# DCDeluxe.net
KiCad netlist of a schematic drawn in EAGLE
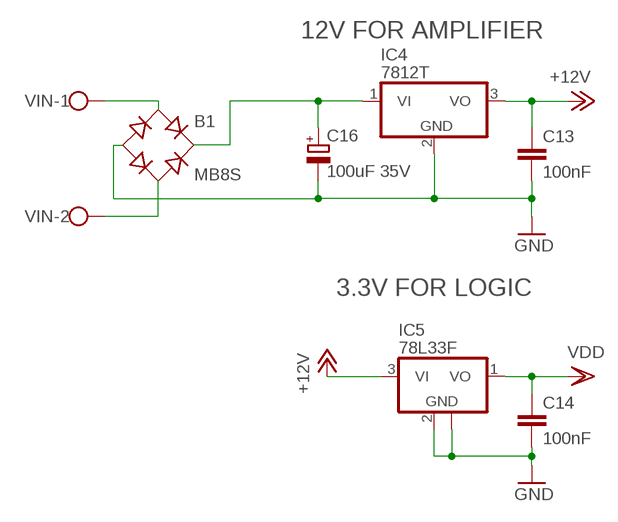
[diagram p0: schematic, sheet 1]
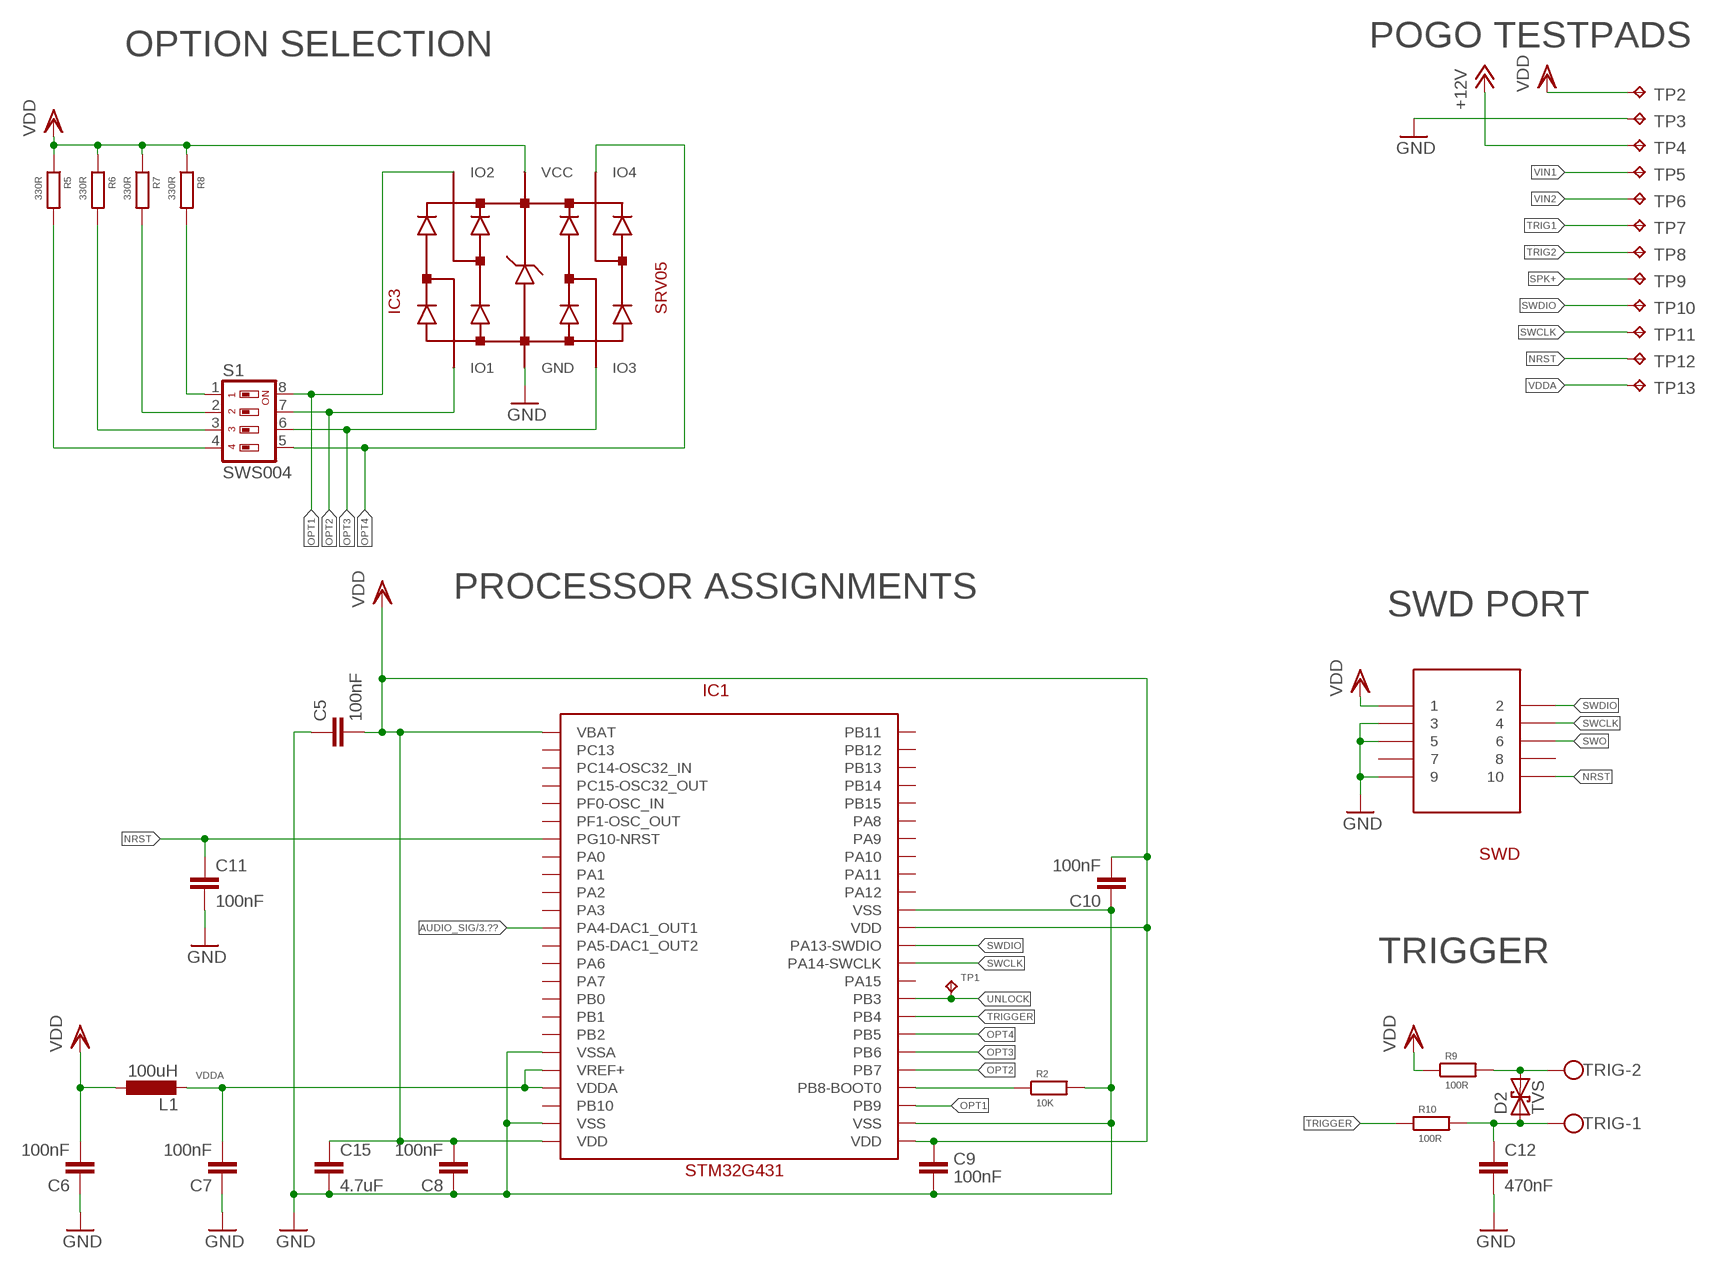
[diagram p1: schematic, sheet 2]
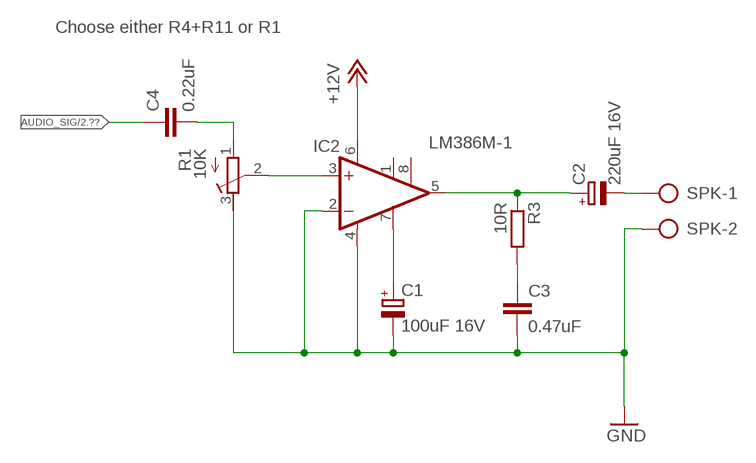
[diagram p2: schematic, sheet 3]

(export (version "E")
  (design (tool "Eeschema 10.0.6"))
  (components
    (comp (ref "B1")
      (value "MB8S")
      (footprint "eagle-import:SOIC-4")
      (libsource (lib "eagle-import") (part "MBS8"))
    )
    (comp (ref "C13")
      (value "100nF")
      (footprint "eagle-import:C0603")
      (libsource (lib "eagle-import") (part "C-EUC0603"))
    )
    (comp (ref "C14")
      (value "100nF")
      (footprint "eagle-import:C0603")
      (libsource (lib "eagle-import") (part "C-EUC0603"))
    )
    (comp (ref "C16")
      (value "100uF 35V")
      (footprint "eagle-import:153CLV-0807")
      (libsource (lib "eagle-import") (part "CPOL-EU153CLV-0807"))
    )
    (comp (ref "IC4")
      (value "7812T")
      (footprint "eagle-import:TO220H")
      (libsource (lib "eagle-import") (part "78T12"))
    )
    (comp (ref "IC5")
      (value "78L33F")
      (footprint "eagle-import:SOT89")
      (libsource (lib "eagle-import") (part "78LF05"))
    )
    (comp (ref "VIN")
      (value "W237-102")
      (footprint "eagle-import:W237-102")
      (fields (field (name "MPN") "237-102"))
      (libsource (lib "eagle-import") (part "W237-102"))
    )
    (comp (ref "C1")
      (value "100uF 16V")
      (footprint "eagle-import:153CLV-0605")
      (libsource (lib "eagle-import") (part "CPOL-EU153CLV-0605"))
    )
    (comp (ref "C2")
      (value "220uF 16V")
      (footprint "eagle-import:153CLV-0605")
      (libsource (lib "eagle-import") (part "CPOL-EU153CLV-0605"))
    )
    (comp (ref "C3")
      (value "0.47uF")
      (footprint "eagle-import:C0603")
      (libsource (lib "eagle-import") (part "C-EUC0603"))
    )
    (comp (ref "C4")
      (value "0.22uF")
      (footprint "eagle-import:C0603")
      (libsource (lib "eagle-import") (part "C-EUC0603"))
    )
    (comp (ref "IC2")
      (value "LM386M-1")
      (footprint "eagle-import:SO08")
      (libsource (lib "eagle-import") (part "LM386?-M1"))
    )
    (comp (ref "R1")
      (value "10K")
      (footprint "eagle-import:RTRIM3339P")
      (libsource (lib "eagle-import") (part "R-TRIMM3339P"))
    )
    (comp (ref "R3")
      (value "10R")
      (footprint "eagle-import:R0805")
      (libsource (lib "eagle-import") (part "R-EU_R0805"))
    )
    (comp (ref "SPK")
      (value "W237-102")
      (footprint "eagle-import:W237-102")
      (fields (field (name "MPN") "237-102"))
      (libsource (lib "eagle-import") (part "W237-102"))
    )
    (comp (ref "C5")
      (value "100nF")
      (footprint "eagle-import:C0603")
      (libsource (lib "eagle-import") (part "C-EUC0603"))
    )
    (comp (ref "C6")
      (value "100nF")
      (footprint "eagle-import:C0603")
      (libsource (lib "eagle-import") (part "C-EUC0603"))
    )
    (comp (ref "C7")
      (value "100nF")
      (footprint "eagle-import:C0603")
      (libsource (lib "eagle-import") (part "C-EUC0603"))
    )
    (comp (ref "C8")
      (value "100nF")
      (footprint "eagle-import:C0603")
      (libsource (lib "eagle-import") (part "C-EUC0603"))
    )
    (comp (ref "C9")
      (value "100nF")
      (footprint "eagle-import:C0603")
      (libsource (lib "eagle-import") (part "C-EUC0603"))
    )
    (comp (ref "C10")
      (value "100nF")
      (footprint "eagle-import:C0603")
      (libsource (lib "eagle-import") (part "C-EUC0603"))
    )
    (comp (ref "C11")
      (value "100nF")
      (footprint "eagle-import:C0603")
      (libsource (lib "eagle-import") (part "C-EUC0603"))
    )
    (comp (ref "C12")
      (value "470nF")
      (footprint "eagle-import:C0603")
      (libsource (lib "eagle-import") (part "C-EUC0603"))
    )
    (comp (ref "C15")
      (value "4.7uF")
      (footprint "eagle-import:C0603")
      (libsource (lib "eagle-import") (part "C-EUC0603"))
    )
    (comp (ref "D2")
      (value "TVS")
      (footprint "eagle-import:SMA-DIODE")
      (libsource (lib "eagle-import") (part "TVS"))
    )
    (comp (ref "IC1")
      (value "STM32G431")
      (footprint "eagle-import:TQFP48")
      (libsource (lib "eagle-import") (part "STM32G431-C8T6"))
    )
    (comp (ref "IC3")
      (value "SRV05")
      (footprint "eagle-import:TSOP-6")
      (libsource (lib "eagle-import") (part "SRV05-TSOP6"))
    )
    (comp (ref "L1")
      (value "100uH")
      (footprint "eagle-import:L3225M")
      (libsource (lib "eagle-import") (part "L-EUL3225M"))
    )
    (comp (ref "R2")
      (value "10K")
      (footprint "eagle-import:R0603")
      (libsource (lib "eagle-import") (part "R-EU_R0603"))
    )
    (comp (ref "R5")
      (value "330R")
      (footprint "eagle-import:R0603")
      (libsource (lib "eagle-import") (part "R-EU_R0603"))
    )
    (comp (ref "R6")
      (value "330R")
      (footprint "eagle-import:R0603")
      (libsource (lib "eagle-import") (part "R-EU_R0603"))
    )
    (comp (ref "R7")
      (value "330R")
      (footprint "eagle-import:R0603")
      (libsource (lib "eagle-import") (part "R-EU_R0603"))
    )
    (comp (ref "R8")
      (value "330R")
      (footprint "eagle-import:R0603")
      (libsource (lib "eagle-import") (part "R-EU_R0603"))
    )
    (comp (ref "R9")
      (value "100R")
      (footprint "eagle-import:R0603")
      (libsource (lib "eagle-import") (part "R-EU_R0603"))
    )
    (comp (ref "R10")
      (value "100R")
      (footprint "eagle-import:R0603")
      (libsource (lib "eagle-import") (part "R-EU_R0603"))
    )
    (comp (ref "S1")
      (value "SWS004")
      (footprint "eagle-import:SMS-004")
      (libsource (lib "eagle-import") (part "SWS004"))
    )
    (comp (ref "SWD")
      (value "FTSH-105-01")
      (footprint "eagle-import:FTSH-105-01-XXX-DV-K")
      (libsource (lib "eagle-import") (part "FTSH-105-01"))
    )
    (comp (ref "TP1")
      (value "TPTP12R")
      (footprint "eagle-import:TP12R")
      (libsource (lib "eagle-import") (part "TPTP12R"))
    )
    (comp (ref "TP2")
      (value "TPTP20R")
      (footprint "eagle-import:TP20R")
      (libsource (lib "eagle-import") (part "TPTP20R"))
    )
    (comp (ref "TP3")
      (value "TPTP20R")
      (footprint "eagle-import:TP20R")
      (libsource (lib "eagle-import") (part "TPTP20R"))
    )
    (comp (ref "TP4")
      (value "TPTP20R")
      (footprint "eagle-import:TP20R")
      (libsource (lib "eagle-import") (part "TPTP20R"))
    )
    (comp (ref "TP5")
      (value "TPTP20R")
      (footprint "eagle-import:TP20R")
      (libsource (lib "eagle-import") (part "TPTP20R"))
    )
    (comp (ref "TP6")
      (value "TPTP20R")
      (footprint "eagle-import:TP20R")
      (libsource (lib "eagle-import") (part "TPTP20R"))
    )
    (comp (ref "TP7")
      (value "TPTP20R")
      (footprint "eagle-import:TP20R")
      (libsource (lib "eagle-import") (part "TPTP20R"))
    )
    (comp (ref "TP8")
      (value "TPTP20R")
      (footprint "eagle-import:TP20R")
      (libsource (lib "eagle-import") (part "TPTP20R"))
    )
    (comp (ref "TP9")
      (value "TPTP20R")
      (footprint "eagle-import:TP20R")
      (libsource (lib "eagle-import") (part "TPTP20R"))
    )
    (comp (ref "TP10")
      (value "TPTP20R")
      (footprint "eagle-import:TP20R")
      (libsource (lib "eagle-import") (part "TPTP20R"))
    )
    (comp (ref "TP11")
      (value "TPTP20R")
      (footprint "eagle-import:TP20R")
      (libsource (lib "eagle-import") (part "TPTP20R"))
    )
    (comp (ref "TP12")
      (value "TPTP20R")
      (footprint "eagle-import:TP20R")
      (libsource (lib "eagle-import") (part "TPTP20R"))
    )
    (comp (ref "TP13")
      (value "TPTP20R")
      (footprint "eagle-import:TP20R")
      (libsource (lib "eagle-import") (part "TPTP20R"))
    )
    (comp (ref "TRIG")
      (value "W237-102")
      (footprint "eagle-import:W237-102")
      (fields (field (name "MPN") "237-102"))
      (libsource (lib "eagle-import") (part "W237-102"))
    )
  )
  (nets
    (net (code "1") (name "+12V") (class "Default")
      (node (ref "C13") (pin "1") (pinfunction "1_1") (pintype "passive"))
      (node (ref "IC2") (pin "6") (pinfunction "VS_6") (pintype "power_in"))
      (node (ref "IC4") (pin "3") (pinfunction "VO_3") (pintype "passive"))
      (node (ref "IC5") (pin "3") (pinfunction "VI_3") (pintype "input"))
      (node (ref "TP4") (pin "TP") (pinfunction "TP_TP") (pintype "input"))
    )
    (net (code "2") (name "AUDIO_SIG") (class "Default")
      (node (ref "C4") (pin "1") (pinfunction "1_1") (pintype "passive"))
      (node (ref "IC1") (pin "PA4-DAC1_OUT1") (pinfunction "PA4-DAC1_OUT1_PA4-DAC1_OUT1") (pintype "bidirectional"))
    )
    (net (code "3") (name "GND") (class "Default")
      (node (ref "B1") (pin "-") (pinfunction "-_-") (pintype "passive"))
      (node (ref "C1") (pin "-") (pinfunction "-_-") (pintype "passive"))
      (node (ref "C10") (pin "1") (pinfunction "1_1") (pintype "passive"))
      (node (ref "C11") (pin "2") (pinfunction "2_2") (pintype "passive"))
      (node (ref "C12") (pin "2") (pinfunction "2_2") (pintype "passive"))
      (node (ref "C13") (pin "2") (pinfunction "2_2") (pintype "passive"))
      (node (ref "C14") (pin "2") (pinfunction "2_2") (pintype "passive"))
      (node (ref "C15") (pin "2") (pinfunction "2_2") (pintype "passive"))
      (node (ref "C16") (pin "-") (pinfunction "-_-") (pintype "passive"))
      (node (ref "C3") (pin "2") (pinfunction "2_2") (pintype "passive"))
      (node (ref "C5") (pin "1") (pinfunction "1_1") (pintype "passive"))
      (node (ref "C6") (pin "1") (pinfunction "1_1") (pintype "passive"))
      (node (ref "C7") (pin "1") (pinfunction "1_1") (pintype "passive"))
      (node (ref "C8") (pin "1") (pinfunction "1_1") (pintype "passive"))
      (node (ref "C9") (pin "1") (pinfunction "1_1") (pintype "passive"))
      (node (ref "IC1") (pin "VSS@23") (pinfunction "VSS_VSS@23") (pintype "power_in"))
      (node (ref "IC1") (pin "VSS@35") (pinfunction "VSS_VSS@35") (pintype "power_in"))
      (node (ref "IC1") (pin "VSS@47") (pinfunction "VSS_VSS@47") (pintype "power_in"))
      (node (ref "IC1") (pin "VSSA") (pinfunction "VSSA_VSSA") (pintype "power_in"))
      (node (ref "IC2") (pin "2") (pinfunction "-IN_2") (pintype "input"))
      (node (ref "IC2") (pin "4") (pinfunction "GND_4") (pintype "power_in"))
      (node (ref "IC3") (pin "GND") (pinfunction "GND_GND") (pintype "bidirectional"))
      (node (ref "IC4") (pin "2") (pinfunction "GND_2") (pintype "passive"))
      (node (ref "IC5") (pin "2") (pinfunction "GND_2") (pintype "passive"))
      (node (ref "IC5") (pin "2@1") (pinfunction "GND_2@1") (pintype "passive"))
      (node (ref "R1") (pin "3") (pinfunction "A_3") (pintype "passive"))
      (node (ref "R2") (pin "2") (pinfunction "2_2") (pintype "passive"))
      (node (ref "SPK") (pin "2") (pinfunction "KL_2") (pintype "passive"))
      (node (ref "SWD") (pin "3") (pinfunction "3_3") (pintype "passive"))
      (node (ref "SWD") (pin "5") (pinfunction "5_5") (pintype "passive"))
      (node (ref "SWD") (pin "9") (pinfunction "9_9") (pintype "passive"))
      (node (ref "TP3") (pin "TP") (pinfunction "TP_TP") (pintype "input"))
    )
    (net (code "4") (name "NRST") (class "Default")
      (node (ref "C11") (pin "1") (pinfunction "1_1") (pintype "passive"))
      (node (ref "IC1") (pin "PG10-NRST") (pinfunction "PG10-NRST_PG10-NRST") (pintype "bidirectional"))
      (node (ref "SWD") (pin "10") (pinfunction "10_10") (pintype "passive"))
      (node (ref "TP12") (pin "TP") (pinfunction "TP_TP") (pintype "input"))
    )
    (net (code "5") (name "Net-(C3-Pad1)") (class "Default")
      (node (ref "C3") (pin "1") (pinfunction "1_1") (pintype "passive"))
      (node (ref "R3") (pin "2") (pinfunction "2_2") (pintype "passive"))
    )
    (net (code "6") (name "Net-(IC1-PadPB8-BOOT0)") (class "Default")
      (node (ref "IC1") (pin "PB8-BOOT0") (pinfunction "PB8-BOOT0_PB8-BOOT0") (pintype "bidirectional"))
      (node (ref "R2") (pin "1") (pinfunction "1_1") (pintype "passive"))
    )
    (net (code "7") (name "Net-(IC2-+IN)") (class "Default")
      (node (ref "IC2") (pin "3") (pinfunction "+IN_3") (pintype "input"))
      (node (ref "R1") (pin "2") (pinfunction "S_2") (pintype "passive"))
    )
    (net (code "8") (name "Net-(IC2-BYPASS)") (class "Default")
      (node (ref "C1") (pin "+") (pinfunction "+_+") (pintype "passive"))
      (node (ref "IC2") (pin "7") (pinfunction "BYPASS_7") (pintype "passive"))
    )
    (net (code "9") (name "Net-(IC2-OUT)") (class "Default")
      (node (ref "C2") (pin "+") (pinfunction "+_+") (pintype "passive"))
      (node (ref "IC2") (pin "5") (pinfunction "OUT_5") (pintype "output"))
      (node (ref "R3") (pin "1") (pinfunction "1_1") (pintype "passive"))
    )
    (net (code "10") (name "Net-(IC4-VI)") (class "Default")
      (node (ref "B1") (pin "+") (pinfunction "+_+") (pintype "passive"))
      (node (ref "C16") (pin "+") (pinfunction "+_+") (pintype "passive"))
      (node (ref "IC4") (pin "1") (pinfunction "VI_1") (pintype "input"))
    )
    (net (code "11") (name "Net-(R1-E)") (class "Default")
      (node (ref "C4") (pin "2") (pinfunction "2_2") (pintype "passive"))
      (node (ref "R1") (pin "1") (pinfunction "E_1") (pintype "passive"))
    )
    (net (code "12") (name "Net-(R5-Pad2)") (class "Default")
      (node (ref "R5") (pin "2") (pinfunction "2_2") (pintype "passive"))
      (node (ref "S1") (pin "4") (pinfunction "4_4") (pintype "passive"))
    )
    (net (code "13") (name "Net-(R6-Pad2)") (class "Default")
      (node (ref "R6") (pin "2") (pinfunction "2_2") (pintype "passive"))
      (node (ref "S1") (pin "3") (pinfunction "3_3") (pintype "passive"))
    )
    (net (code "14") (name "Net-(R7-Pad2)") (class "Default")
      (node (ref "R7") (pin "2") (pinfunction "2_2") (pintype "passive"))
      (node (ref "S1") (pin "2") (pinfunction "2_2") (pintype "passive"))
    )
    (net (code "15") (name "Net-(R8-Pad2)") (class "Default")
      (node (ref "R8") (pin "2") (pinfunction "2_2") (pintype "passive"))
      (node (ref "S1") (pin "1") (pinfunction "1_1") (pintype "passive"))
    )
    (net (code "16") (name "OPT1") (class "Default")
      (node (ref "IC1") (pin "PB9") (pinfunction "PB9_PB9") (pintype "bidirectional"))
      (node (ref "IC3") (pin "IO2") (pinfunction "IO2_IO2") (pintype "bidirectional"))
      (node (ref "S1") (pin "8") (pinfunction "8_8") (pintype "passive"))
    )
    (net (code "17") (name "OPT2") (class "Default")
      (node (ref "IC1") (pin "PB7") (pinfunction "PB7_PB7") (pintype "bidirectional"))
      (node (ref "IC3") (pin "IO1") (pinfunction "IO1_IO1") (pintype "bidirectional"))
      (node (ref "S1") (pin "7") (pinfunction "7_7") (pintype "passive"))
    )
    (net (code "18") (name "OPT3") (class "Default")
      (node (ref "IC1") (pin "PB6") (pinfunction "PB6_PB6") (pintype "bidirectional"))
      (node (ref "IC3") (pin "IO3") (pinfunction "IO3_IO3") (pintype "bidirectional"))
      (node (ref "S1") (pin "6") (pinfunction "6_6") (pintype "passive"))
    )
    (net (code "19") (name "OPT4") (class "Default")
      (node (ref "IC1") (pin "PB5") (pinfunction "PB5_PB5") (pintype "bidirectional"))
      (node (ref "IC3") (pin "IO4") (pinfunction "IO4_IO4") (pintype "bidirectional"))
      (node (ref "S1") (pin "5") (pinfunction "5_5") (pintype "passive"))
    )
    (net (code "20") (name "SPK+") (class "Default")
      (node (ref "C2") (pin "-") (pinfunction "-_-") (pintype "passive"))
      (node (ref "SPK") (pin "1") (pinfunction "KL_1") (pintype "passive"))
      (node (ref "TP9") (pin "TP") (pinfunction "TP_TP") (pintype "input"))
    )
    (net (code "21") (name "SWCLK") (class "Default")
      (node (ref "IC1") (pin "PA14-SWCLK") (pinfunction "PA14-SWCLK_PA14-SWCLK") (pintype "bidirectional"))
      (node (ref "SWD") (pin "4") (pinfunction "4_4") (pintype "passive"))
      (node (ref "TP11") (pin "TP") (pinfunction "TP_TP") (pintype "input"))
    )
    (net (code "22") (name "SWDIO") (class "Default")
      (node (ref "IC1") (pin "PA13-SWDIO") (pinfunction "PA13-SWDIO_PA13-SWDIO") (pintype "bidirectional"))
      (node (ref "SWD") (pin "2") (pinfunction "2_2") (pintype "passive"))
      (node (ref "TP10") (pin "TP") (pinfunction "TP_TP") (pintype "input"))
    )
    (net (code "23") (name "SWO") (class "Default")
      (node (ref "SWD") (pin "6") (pinfunction "6_6") (pintype "passive"))
    )
    (net (code "24") (name "TRIG1") (class "Default")
      (node (ref "C12") (pin "1") (pinfunction "1_1") (pintype "passive"))
      (node (ref "D2") (pin "A") (pinfunction "1_A") (pintype "passive"))
      (node (ref "R10") (pin "2") (pinfunction "2_2") (pintype "passive"))
      (node (ref "TP7") (pin "TP") (pinfunction "TP_TP") (pintype "input"))
      (node (ref "TRIG") (pin "1") (pinfunction "KL_1") (pintype "passive"))
    )
    (net (code "25") (name "TRIG2") (class "Default")
      (node (ref "D2") (pin "C") (pinfunction "2_C") (pintype "passive"))
      (node (ref "R9") (pin "2") (pinfunction "2_2") (pintype "passive"))
      (node (ref "TP8") (pin "TP") (pinfunction "TP_TP") (pintype "input"))
      (node (ref "TRIG") (pin "2") (pinfunction "KL_2") (pintype "passive"))
    )
    (net (code "26") (name "TRIGGER") (class "Default")
      (node (ref "IC1") (pin "PB4") (pinfunction "PB4_PB4") (pintype "bidirectional"))
      (node (ref "R10") (pin "1") (pinfunction "1_1") (pintype "passive"))
    )
    (net (code "27") (name "UNLOCK") (class "Default")
      (node (ref "IC1") (pin "PB3") (pinfunction "PB3_PB3") (pintype "bidirectional"))
      (node (ref "TP1") (pin "TP") (pinfunction "TP_TP") (pintype "input"))
    )
    (net (code "28") (name "VDD") (class "Default")
      (node (ref "C10") (pin "2") (pinfunction "2_2") (pintype "passive"))
      (node (ref "C14") (pin "1") (pinfunction "1_1") (pintype "passive"))
      (node (ref "C15") (pin "1") (pinfunction "1_1") (pintype "passive"))
      (node (ref "C5") (pin "2") (pinfunction "2_2") (pintype "passive"))
      (node (ref "C6") (pin "2") (pinfunction "2_2") (pintype "passive"))
      (node (ref "C8") (pin "2") (pinfunction "2_2") (pintype "passive"))
      (node (ref "C9") (pin "2") (pinfunction "2_2") (pintype "passive"))
      (node (ref "IC1") (pin "VBAT") (pinfunction "VBAT_VBAT") (pintype "power_in"))
      (node (ref "IC1") (pin "VDD@24") (pinfunction "VDD_VDD@24") (pintype "power_in"))
      (node (ref "IC1") (pin "VDD@36") (pinfunction "VDD_VDD@36") (pintype "power_in"))
      (node (ref "IC1") (pin "VDD@48") (pinfunction "VDD_VDD@48") (pintype "power_in"))
      (node (ref "IC3") (pin "VCC") (pinfunction "VCC_VCC") (pintype "bidirectional"))
      (node (ref "IC5") (pin "1") (pinfunction "VO_1") (pintype "passive"))
      (node (ref "L1") (pin "1") (pinfunction "1_1") (pintype "passive"))
      (node (ref "R5") (pin "1") (pinfunction "1_1") (pintype "passive"))
      (node (ref "R6") (pin "1") (pinfunction "1_1") (pintype "passive"))
      (node (ref "R7") (pin "1") (pinfunction "1_1") (pintype "passive"))
      (node (ref "R8") (pin "1") (pinfunction "1_1") (pintype "passive"))
      (node (ref "R9") (pin "1") (pinfunction "1_1") (pintype "passive"))
      (node (ref "SWD") (pin "1") (pinfunction "1_1") (pintype "passive"))
      (node (ref "TP2") (pin "TP") (pinfunction "TP_TP") (pintype "input"))
    )
    (net (code "29") (name "VDDA") (class "Default")
      (node (ref "C7") (pin "2") (pinfunction "2_2") (pintype "passive"))
      (node (ref "IC1") (pin "VDDA") (pinfunction "VDDA_VDDA") (pintype "power_in"))
      (node (ref "IC1") (pin "VREF+") (pinfunction "VREF+_VREF+") (pintype "power_in"))
      (node (ref "L1") (pin "2") (pinfunction "2_2") (pintype "passive"))
      (node (ref "TP13") (pin "TP") (pinfunction "TP_TP") (pintype "input"))
    )
    (net (code "30") (name "VIN1") (class "Default")
      (node (ref "B1") (pin "~1") (pinfunction "AC1_~1") (pintype "passive"))
      (node (ref "TP5") (pin "TP") (pinfunction "TP_TP") (pintype "input"))
      (node (ref "VIN") (pin "1") (pinfunction "KL_1") (pintype "passive"))
    )
    (net (code "31") (name "VIN2") (class "Default")
      (node (ref "B1") (pin "~2") (pinfunction "AC2_~2") (pintype "passive"))
      (node (ref "TP6") (pin "TP") (pinfunction "TP_TP") (pintype "input"))
      (node (ref "VIN") (pin "2") (pinfunction "KL_2") (pintype "passive"))
    )
    (net (code "32") (name "unconnected-(IC1-PadPA0)") (class "Default")
      (node (ref "IC1") (pin "PA0") (pinfunction "PA0_PA0") (pintype "bidirectional"))
    )
    (net (code "33") (name "unconnected-(IC1-PadPA1)") (class "Default")
      (node (ref "IC1") (pin "PA1") (pinfunction "PA1_PA1") (pintype "bidirectional"))
    )
    (net (code "34") (name "unconnected-(IC1-PadPA2)") (class "Default")
      (node (ref "IC1") (pin "PA2") (pinfunction "PA2_PA2") (pintype "bidirectional"))
    )
    (net (code "35") (name "unconnected-(IC1-PadPA3)") (class "Default")
      (node (ref "IC1") (pin "PA3") (pinfunction "PA3_PA3") (pintype "bidirectional"))
    )
    (net (code "36") (name "unconnected-(IC1-PadPA5-DAC1_OUT2)") (class "Default")
      (node (ref "IC1") (pin "PA5-DAC1_OUT2") (pinfunction "PA5-DAC1_OUT2_PA5-DAC1_OUT2") (pintype "bidirectional"))
    )
    (net (code "37") (name "unconnected-(IC1-PadPA6)") (class "Default")
      (node (ref "IC1") (pin "PA6") (pinfunction "PA6_PA6") (pintype "bidirectional"))
    )
    (net (code "38") (name "unconnected-(IC1-PadPA7)") (class "Default")
      (node (ref "IC1") (pin "PA7") (pinfunction "PA7_PA7") (pintype "bidirectional"))
    )
    (net (code "39") (name "unconnected-(IC1-PadPA8)") (class "Default")
      (node (ref "IC1") (pin "PA8") (pinfunction "PA8_PA8") (pintype "bidirectional"))
    )
    (net (code "40") (name "unconnected-(IC1-PadPA9)") (class "Default")
      (node (ref "IC1") (pin "PA9") (pinfunction "PA9_PA9") (pintype "bidirectional"))
    )
    (net (code "41") (name "unconnected-(IC1-PadPA10)") (class "Default")
      (node (ref "IC1") (pin "PA10") (pinfunction "PA10_PA10") (pintype "bidirectional"))
    )
    (net (code "42") (name "unconnected-(IC1-PadPA11)") (class "Default")
      (node (ref "IC1") (pin "PA11") (pinfunction "PA11_PA11") (pintype "bidirectional"))
    )
    (net (code "43") (name "unconnected-(IC1-PadPA12)") (class "Default")
      (node (ref "IC1") (pin "PA12") (pinfunction "PA12_PA12") (pintype "bidirectional"))
    )
    (net (code "44") (name "unconnected-(IC1-PadPA15)") (class "Default")
      (node (ref "IC1") (pin "PA15") (pinfunction "PA15_PA15") (pintype "bidirectional"))
    )
    (net (code "45") (name "unconnected-(IC1-PadPB0)") (class "Default")
      (node (ref "IC1") (pin "PB0") (pinfunction "PB0_PB0") (pintype "bidirectional"))
    )
    (net (code "46") (name "unconnected-(IC1-PadPB1)") (class "Default")
      (node (ref "IC1") (pin "PB1") (pinfunction "PB1_PB1") (pintype "bidirectional"))
    )
    (net (code "47") (name "unconnected-(IC1-PadPB2)") (class "Default")
      (node (ref "IC1") (pin "PB2") (pinfunction "PB2_PB2") (pintype "bidirectional"))
    )
    (net (code "48") (name "unconnected-(IC1-PadPB10)") (class "Default")
      (node (ref "IC1") (pin "PB10") (pinfunction "PB10_PB10") (pintype "bidirectional"))
    )
    (net (code "49") (name "unconnected-(IC1-PadPB11)") (class "Default")
      (node (ref "IC1") (pin "PB11") (pinfunction "PB11_PB11") (pintype "bidirectional"))
    )
    (net (code "50") (name "unconnected-(IC1-PadPB12)") (class "Default")
      (node (ref "IC1") (pin "PB12") (pinfunction "PB12_PB12") (pintype "bidirectional"))
    )
    (net (code "51") (name "unconnected-(IC1-PadPB13)") (class "Default")
      (node (ref "IC1") (pin "PB13") (pinfunction "PB13_PB13") (pintype "bidirectional"))
    )
    (net (code "52") (name "unconnected-(IC1-PadPB14)") (class "Default")
      (node (ref "IC1") (pin "PB14") (pinfunction "PB14_PB14") (pintype "bidirectional"))
    )
    (net (code "53") (name "unconnected-(IC1-PadPB15)") (class "Default")
      (node (ref "IC1") (pin "PB15") (pinfunction "PB15_PB15") (pintype "bidirectional"))
    )
    (net (code "54") (name "unconnected-(IC1-PadPC13)") (class "Default")
      (node (ref "IC1") (pin "PC13") (pinfunction "PC13_PC13") (pintype "bidirectional"))
    )
    (net (code "55") (name "unconnected-(IC1-PadPC14-OSC32_IN)") (class "Default")
      (node (ref "IC1") (pin "PC14-OSC32_IN") (pinfunction "PC14-OSC32_IN_PC14-OSC32_IN") (pintype "bidirectional"))
    )
    (net (code "56") (name "unconnected-(IC1-PadPC15-OSC32_OUT)") (class "Default")
      (node (ref "IC1") (pin "PC15-OSC32_OUT") (pinfunction "PC15-OSC32_OUT_PC15-OSC32_OUT") (pintype "bidirectional"))
    )
    (net (code "57") (name "unconnected-(IC1-PadPF0-OSC_IN)") (class "Default")
      (node (ref "IC1") (pin "PF0-OSC_IN") (pinfunction "PF0-OSC_IN_PF0-OSC_IN") (pintype "bidirectional"))
    )
    (net (code "58") (name "unconnected-(IC1-PadPF1-OSC_OUT)") (class "Default")
      (node (ref "IC1") (pin "PF1-OSC_OUT") (pinfunction "PF1-OSC_OUT_PF1-OSC_OUT") (pintype "bidirectional"))
    )
    (net (code "59") (name "unconnected-(IC2-GAIN-Pad1)") (class "Default")
      (node (ref "IC2") (pin "1") (pinfunction "GAIN_1") (pintype "passive"))
    )
    (net (code "60") (name "unconnected-(IC2-GAIN-Pad8)") (class "Default")
      (node (ref "IC2") (pin "8") (pinfunction "GAIN_8") (pintype "passive"))
    )
    (net (code "61") (name "unconnected-(SWD-Pad7)") (class "Default")
      (node (ref "SWD") (pin "7") (pinfunction "7_7") (pintype "passive"))
    )
    (net (code "62") (name "unconnected-(SWD-Pad8)") (class "Default")
      (node (ref "SWD") (pin "8") (pinfunction "8_8") (pintype "passive"))
    )
  )
)
